# 08_CoreBoard.net
KiCad netlist of a schematic drawn in Altium Designer
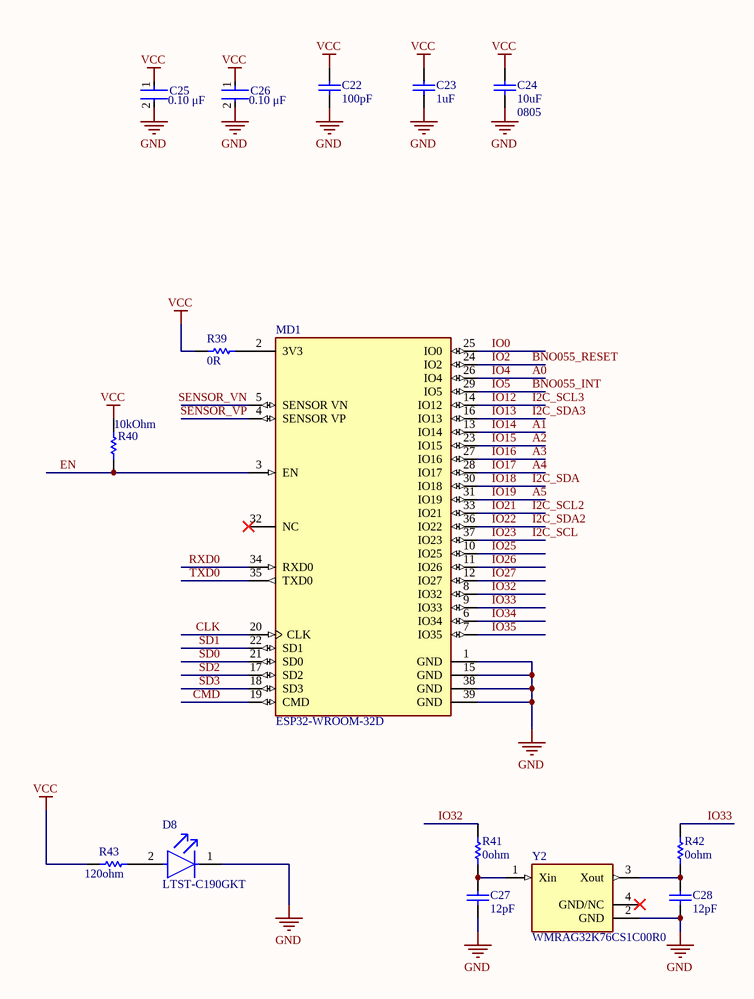
[diagram p0: 08_CoreBoard.SchDoc]

(export (version "E")
  (design (tool "Eeschema 10.0.6"))
  (components
    (comp (ref "C22")
      (value "100pF")
      (footprint "CAPC1608X87X35LL15T15")
      (fields (field (name "MANUFACTURER") "Kemet") (field (name "PART NUMBER") "C0603C101J1GACTU"))
      (libsource (lib "Altium Content Vault") (part "CAP"))
    )
    (comp (ref "C23")
      (value "1uF")
      (footprint "CAPC1608X87X35LL15T15")
      (fields (field (name "MANUFACTURER") "Kemet") (field (name "PART NUMBER") "C0603C101J1GACTU"))
      (libsource (lib "Altium Content Vault") (part "CAP"))
    )
    (comp (ref "C24")
      (value "10uF")
      (footprint "CAPC2013X135X50LL10T20")
      (fields
        (field (name "MANUFACTURER") "Murata")
        (field (name "PART NUMBER") "GRM21BR61C106KE15L")
        (field (name "PACKAGE") "0805")
      )
      (libsource (lib "Altium Content Vault") (part "CAP"))
    )
    (comp (ref "C25")
      (value "C0603C104M4RAC7411")
      (footprint "FP-C0603C-CF-MFG")
      (description "CAP CER 0.1UF 16V X7R 0603")
      (fields
        (field (name "TOLERANCE") "0.2")
        (field (name "CAPACITANCE") "0.10 μF")
        (field (name "MANUFACTURER") "KEMET")
      )
      (libsource (lib "Altium Content Vault") (part "b4654b650e69147ec39a6b967a45e02"))
    )
    (comp (ref "C26")
      (value "C0603C104M4RAC7411")
      (footprint "FP-C0603C-CF-MFG")
      (description "CAP CER 0.1UF 16V X7R 0603")
      (fields
        (field (name "TOLERANCE") "0.2")
        (field (name "CAPACITANCE") "0.10 μF")
        (field (name "MANUFACTURER") "KEMET")
      )
      (libsource (lib "Altium Content Vault") (part "b4654b650e69147ec39a6b967a45e02"))
    )
    (comp (ref "C27")
      (value "12pF")
      (footprint "CAPC1608X90X40NL10T20")
      (description "Chip Capacitor, 12 pF, +/- 5%, 50 V, -55 to 125 degC, 0603 (1608 Metric), RoHS, Tape and Reel")
      (fields (field (name "TOLERANCE") "1%") (field (name "Comment") "CC0603JRNPO9BN120"))
      (libsource (lib "Altium Content Vault") (part "CAP-NP-2"))
    )
    (comp (ref "C28")
      (value "12pF")
      (footprint "CAPC1608X90X40NL10T20")
      (description "Chip Capacitor, 12 pF, +/- 5%, 50 V, -55 to 125 degC, 0603 (1608 Metric), RoHS, Tape and Reel")
      (fields (field (name "TOLERANCE") "1%") (field (name "Comment") "CC0603JRNPO9BN120"))
      (libsource (lib "Altium Content Vault") (part "CAP-NP-2"))
    )
    (comp (ref "D8")
      (value "LTST-C190GKT")
      (footprint "FP-LTST-C190GKT-MFG")
      (description "LED GREEN CLEAR CHIP SMD")
      (fields (field (name "VOLTAGE") "2V"))
      (libsource (lib "Altium Content Vault") (part "8706943c75ba83719d021d2fdc84c58"))
    )
    (comp (ref "MD1")
      (value "ESP32-WROOM-32D")
      (footprint "FP-ESP32-WROOM-32D-MFG")
      (description "WIFI MODULE 32MBITS SPI FLASH")
      (fields
        (field (name "OCTOPART") "https://octopart.com/esp32-wroom-32d-espressif+systems-91040050")
        (field (name "MANUFACTURER") "Espressif Systems")
      )
      (libsource (lib "Altium Content Vault") (part "a031a76f8c27026a7a7f4657ff233a3"))
    )
    (comp (ref "R39")
      (value "0R")
      (footprint "RESC1608X55X25ML10T15")
      (description "Chip Resistor, 0 Ohm, +/- 5%, 0.1 W, -55 to 155 degC, 0603 (1608 Metric), RoHS, Tape and Reel")
      (fields (field (name "TOLERANCE") "5%") (field (name "MANUFACTURER") "Yageo"))
      (libsource (lib "Altium Content Vault") (part "RES-2"))
    )
    (comp (ref "R40")
      (value "RC0603JR-0710KL")
      (footprint "RESC1608X55X25ML10T15")
      (description "Resistor, 10 KOhm, +/- 5%, 100 mW, -55 to 155 degC, 0603 (1608 Metric), RoHS, Tape and Reel")
      (fields
        (field (name "RESISTANCE") "10kOhm")
        (field (name "MANUFACTURER") "Yageo")
        (field (name "TOLERANCE") "5%")
      )
      (libsource (lib "Altium Content Vault") (part "RES-2"))
    )
    (comp (ref "R41")
      (value "0ohm")
      (footprint "RESC1608X55X25ML10T15")
      (description "Chip Resistor, 0 Ohm, +/- 5%, 0.1 W, -55 to 155 degC, 0603 (1608 Metric), RoHS, Tape and Reel")
      (fields (field (name "TOLERANCE") "5%") (field (name "MANUFACTURER") "Yageo"))
      (libsource (lib "Altium Content Vault") (part "RES-2"))
    )
    (comp (ref "R42")
      (value "0ohm")
      (footprint "RESC1608X55X25ML10T15")
      (description "Chip Resistor, 0 Ohm, +/- 5%, 0.1 W, -55 to 155 degC, 0603 (1608 Metric), RoHS, Tape and Reel")
      (fields (field (name "TOLERANCE") "5%") (field (name "MANUFACTURER") "Yageo"))
      (libsource (lib "Altium Content Vault") (part "RES-2"))
    )
    (comp (ref "R43")
      (value "120ohm")
      (footprint "RESC1608X55X30NL20T20")
      (fields (field (name "PART NUMBER") "ERA-3AEB121V") (field (name "MANUFACTURER") "Panasonic"))
      (libsource (lib "Altium Content Vault") (part "RES"))
    )
    (comp (ref "Y2")
      (value "WMRAG32K76CS1C00R0")
      (footprint "FP-WMRAG32K76CS1C00R0-MFG")
      (description "MEMS Resonator")
      (fields (field (name "TOLERANCE") "20ppm") (field (name "MANUFACTURER") "Murata"))
      (libsource (lib "Altium Content Vault") (part "f3e38fa55a21b72a83ee03d0b531324"))
    )
  )
  (nets
    (net (code "1") (name "/A0") (class "Default")
      (node (ref "MD1") (pin "26") (pinfunction "IO4_26") (pintype "bidirectional"))
    )
    (net (code "2") (name "/A1") (class "Default")
      (node (ref "MD1") (pin "13") (pinfunction "IO14_13") (pintype "bidirectional"))
    )
    (net (code "3") (name "/A2") (class "Default")
      (node (ref "MD1") (pin "23") (pinfunction "IO15_23") (pintype "bidirectional"))
    )
    (net (code "4") (name "/A3") (class "Default")
      (node (ref "MD1") (pin "27") (pinfunction "IO16_27") (pintype "bidirectional"))
    )
    (net (code "5") (name "/A4") (class "Default")
      (node (ref "MD1") (pin "28") (pinfunction "IO17_28") (pintype "bidirectional"))
    )
    (net (code "6") (name "/A5") (class "Default")
      (node (ref "MD1") (pin "31") (pinfunction "IO19_31") (pintype "bidirectional"))
    )
    (net (code "7") (name "/BNO055_INT") (class "Default")
      (node (ref "MD1") (pin "29") (pinfunction "IO5_29") (pintype "bidirectional"))
    )
    (net (code "8") (name "/BNO055_RESET") (class "Default")
      (node (ref "MD1") (pin "24") (pinfunction "IO2_24") (pintype "bidirectional"))
    )
    (net (code "9") (name "/CLK") (class "Default")
      (node (ref "MD1") (pin "20") (pinfunction "CLK_20") (pintype "input"))
    )
    (net (code "10") (name "/CMD") (class "Default")
      (node (ref "MD1") (pin "19") (pinfunction "CMD_19") (pintype "bidirectional"))
    )
    (net (code "11") (name "/EN") (class "Default")
      (node (ref "MD1") (pin "3") (pinfunction "EN_3") (pintype "input"))
      (node (ref "R40") (pin "1") (pinfunction "1_1") (pintype "passive"))
    )
    (net (code "12") (name "/I2C_SCL") (class "Default")
      (node (ref "MD1") (pin "37") (pinfunction "IO23_37") (pintype "bidirectional"))
    )
    (net (code "13") (name "/I2C_SCL2") (class "Default")
      (node (ref "MD1") (pin "33") (pinfunction "IO21_33") (pintype "bidirectional"))
    )
    (net (code "14") (name "/I2C_SCL3") (class "Default")
      (node (ref "MD1") (pin "14") (pinfunction "IO12_14") (pintype "bidirectional"))
    )
    (net (code "15") (name "/I2C_SDA") (class "Default")
      (node (ref "MD1") (pin "30") (pinfunction "IO18_30") (pintype "bidirectional"))
    )
    (net (code "16") (name "/I2C_SDA2") (class "Default")
      (node (ref "MD1") (pin "36") (pinfunction "IO22_36") (pintype "bidirectional"))
    )
    (net (code "17") (name "/I2C_SDA3") (class "Default")
      (node (ref "MD1") (pin "16") (pinfunction "IO13_16") (pintype "bidirectional"))
    )
    (net (code "18") (name "/IO0") (class "Default")
      (node (ref "MD1") (pin "25") (pinfunction "IO0_25") (pintype "bidirectional"))
    )
    (net (code "19") (name "/IO25") (class "Default")
      (node (ref "MD1") (pin "10") (pinfunction "IO25_10") (pintype "bidirectional"))
    )
    (net (code "20") (name "/IO26") (class "Default")
      (node (ref "MD1") (pin "11") (pinfunction "IO26_11") (pintype "bidirectional"))
    )
    (net (code "21") (name "/IO27") (class "Default")
      (node (ref "MD1") (pin "12") (pinfunction "IO27_12") (pintype "bidirectional"))
    )
    (net (code "22") (name "/IO32") (class "Default")
      (node (ref "MD1") (pin "8") (pinfunction "IO32_8") (pintype "bidirectional"))
      (node (ref "R41") (pin "1") (pinfunction "1_1") (pintype "passive"))
    )
    (net (code "23") (name "/IO33") (class "Default")
      (node (ref "MD1") (pin "9") (pinfunction "IO33_9") (pintype "bidirectional"))
      (node (ref "R42") (pin "1") (pinfunction "1_1") (pintype "passive"))
    )
    (net (code "24") (name "/IO34") (class "Default")
      (node (ref "MD1") (pin "6") (pinfunction "IO34_6") (pintype "bidirectional"))
    )
    (net (code "25") (name "/IO35") (class "Default")
      (node (ref "MD1") (pin "7") (pinfunction "IO35_7") (pintype "bidirectional"))
    )
    (net (code "26") (name "/RXD0") (class "Default")
      (node (ref "MD1") (pin "34") (pinfunction "RXD0_34") (pintype "input"))
    )
    (net (code "27") (name "/SD0") (class "Default")
      (node (ref "MD1") (pin "21") (pinfunction "SD0_21") (pintype "bidirectional"))
    )
    (net (code "28") (name "/SD1") (class "Default")
      (node (ref "MD1") (pin "22") (pinfunction "SD1_22") (pintype "bidirectional"))
    )
    (net (code "29") (name "/SD2") (class "Default")
      (node (ref "MD1") (pin "17") (pinfunction "SD2_17") (pintype "bidirectional"))
    )
    (net (code "30") (name "/SD3") (class "Default")
      (node (ref "MD1") (pin "18") (pinfunction "SD3_18") (pintype "bidirectional"))
    )
    (net (code "31") (name "/SENSOR_VN") (class "Default")
      (node (ref "MD1") (pin "5") (pinfunction "SENSOR_VN_5") (pintype "bidirectional"))
    )
    (net (code "32") (name "/SENSOR_VP") (class "Default")
      (node (ref "MD1") (pin "4") (pinfunction "SENSOR_VP_4") (pintype "bidirectional"))
    )
    (net (code "33") (name "/TXD0") (class "Default")
      (node (ref "MD1") (pin "35") (pinfunction "TXD0_35") (pintype "output"))
    )
    (net (code "34") (name "GND") (class "Default")
      (node (ref "C22") (pin "1") (pinfunction "1_1") (pintype "passive"))
      (node (ref "C23") (pin "1") (pinfunction "1_1") (pintype "passive"))
      (node (ref "C24") (pin "1") (pinfunction "1_1") (pintype "passive"))
      (node (ref "C25") (pin "2") (pinfunction "2_2") (pintype "passive"))
      (node (ref "C26") (pin "2") (pinfunction "2_2") (pintype "passive"))
      (node (ref "C27") (pin "1") (pinfunction "1_1") (pintype "passive"))
      (node (ref "C28") (pin "1") (pinfunction "1_1") (pintype "passive"))
      (node (ref "D8") (pin "1") (pinfunction "C_1") (pintype "passive"))
      (node (ref "MD1") (pin "1") (pinfunction "GND_1") (pintype "power_in"))
      (node (ref "MD1") (pin "15") (pinfunction "GND_15") (pintype "power_in"))
      (node (ref "MD1") (pin "38") (pinfunction "GND_38") (pintype "power_in"))
      (node (ref "MD1") (pin "39") (pinfunction "GND_39") (pintype "power_in"))
      (node (ref "Y2") (pin "2") (pinfunction "GND_2") (pintype "power_in"))
    )
    (net (code "35") (name "Net-(D8-A)") (class "Default")
      (node (ref "D8") (pin "2") (pinfunction "A_2") (pintype "passive"))
      (node (ref "R43") (pin "2") (pinfunction "2_2") (pintype "passive"))
    )
    (net (code "36") (name "Net-(MD1-3V3)") (class "Default")
      (node (ref "MD1") (pin "2") (pinfunction "3V3_2") (pintype "power_in"))
      (node (ref "R39") (pin "2") (pinfunction "2_2") (pintype "passive"))
    )
    (net (code "37") (name "Net-(Y2-Xin)") (class "Default")
      (node (ref "C27") (pin "2") (pinfunction "2_2") (pintype "passive"))
      (node (ref "R41") (pin "2") (pinfunction "2_2") (pintype "passive"))
      (node (ref "Y2") (pin "1") (pinfunction "Xin_1") (pintype "input"))
    )
    (net (code "38") (name "Net-(Y2-Xout)") (class "Default")
      (node (ref "C28") (pin "2") (pinfunction "2_2") (pintype "passive"))
      (node (ref "R42") (pin "2") (pinfunction "2_2") (pintype "passive"))
      (node (ref "Y2") (pin "3") (pinfunction "Xout_3") (pintype "output"))
    )
    (net (code "39") (name "VCC") (class "Default")
      (node (ref "C22") (pin "2") (pinfunction "2_2") (pintype "passive"))
      (node (ref "C23") (pin "2") (pinfunction "2_2") (pintype "passive"))
      (node (ref "C24") (pin "2") (pinfunction "2_2") (pintype "passive"))
      (node (ref "C25") (pin "1") (pinfunction "1_1") (pintype "passive"))
      (node (ref "C26") (pin "1") (pinfunction "1_1") (pintype "passive"))
      (node (ref "R39") (pin "1") (pinfunction "1_1") (pintype "passive"))
      (node (ref "R40") (pin "2") (pinfunction "2_2") (pintype "passive"))
      (node (ref "R43") (pin "1") (pinfunction "1_1") (pintype "passive"))
    )
    (net (code "40") (name "unconnected-(MD1-NC-Pad32)") (class "Default")
      (node (ref "MD1") (pin "32") (pinfunction "NC_32") (pintype "passive+no_connect"))
    )
    (net (code "41") (name "unconnected-(Y2-GND{slash}NC-Pad4)") (class "Default")
      (node (ref "Y2") (pin "4") (pinfunction "GND/NC_4") (pintype "passive+no_connect"))
    )
  )
)
